# Rocky_Switch_Relay_Shield.net
KiCad netlist of a schematic drawn in EAGLE
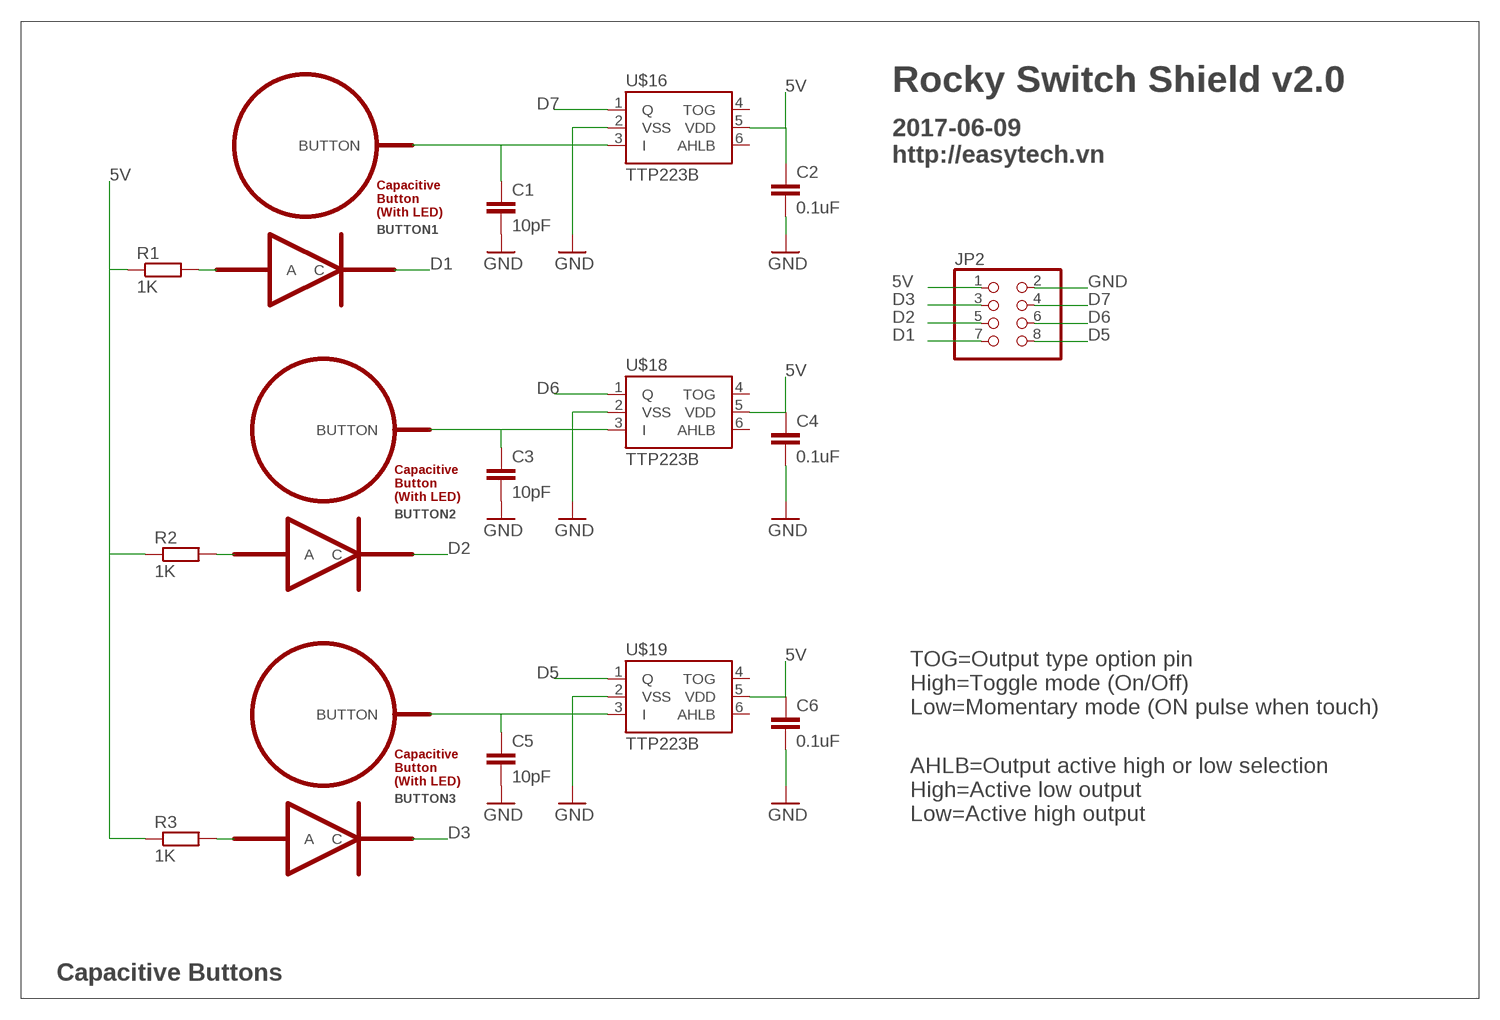
[diagram p0: schematic, sheet 1]

(export (version "E")
  (design (tool "Eeschema 10.0.6"))
  (components
    (comp (ref "BUTTON1")
      (value "BUTTON_PASSIVE_LED")
      (footprint "eagle-import:BUTTON_PASSIVE_LED")
      (libsource (lib "eagle-import") (part "BUTTON_PASSIVE_LED"))
    )
    (comp (ref "BUTTON2")
      (value "BUTTON_PASSIVE_LED")
      (footprint "eagle-import:BUTTON_PASSIVE_LED")
      (libsource (lib "eagle-import") (part "BUTTON_PASSIVE_LED"))
    )
    (comp (ref "BUTTON3")
      (value "BUTTON_PASSIVE_LED")
      (footprint "eagle-import:BUTTON_PASSIVE_LED")
      (libsource (lib "eagle-import") (part "BUTTON_PASSIVE_LED"))
    )
    (comp (ref "C1")
      (value "10pF")
      (footprint "eagle-import:C0805K")
      (libsource (lib "eagle-import") (part "C-EUC0805K"))
    )
    (comp (ref "C2")
      (value "0.1uF")
      (footprint "eagle-import:C0805K")
      (libsource (lib "eagle-import") (part "C-EUC0805K"))
    )
    (comp (ref "C3")
      (value "10pF")
      (footprint "eagle-import:C0805K")
      (libsource (lib "eagle-import") (part "C-EUC0805K"))
    )
    (comp (ref "C4")
      (value "0.1uF")
      (footprint "eagle-import:C0805K")
      (libsource (lib "eagle-import") (part "C-EUC0805K"))
    )
    (comp (ref "C5")
      (value "10pF")
      (footprint "eagle-import:C0805K")
      (libsource (lib "eagle-import") (part "C-EUC0805K"))
    )
    (comp (ref "C6")
      (value "0.1uF")
      (footprint "eagle-import:C0805K")
      (libsource (lib "eagle-import") (part "C-EUC0805K"))
    )
    (comp (ref "JP2")
      (value "PINHD-2X4")
      (footprint "eagle-import:2X04")
      (libsource (lib "eagle-import") (part "PINHD-2X4"))
    )
    (comp (ref "R1")
      (value "1K")
      (footprint "eagle-import:R0805")
      (libsource (lib "eagle-import") (part "R-EU_R0805"))
    )
    (comp (ref "R2")
      (value "1K")
      (footprint "eagle-import:R0805")
      (libsource (lib "eagle-import") (part "R-EU_R0805"))
    )
    (comp (ref "R3")
      (value "1K")
      (footprint "eagle-import:R0805")
      (libsource (lib "eagle-import") (part "R-EU_R0805"))
    )
    (comp (ref "U$16")
      (value "TTP223B")
      (footprint "eagle-import:SOT23-6")
      (libsource (lib "eagle-import") (part "TTP223B"))
    )
    (comp (ref "U$18")
      (value "TTP223B")
      (footprint "eagle-import:SOT23-6")
      (libsource (lib "eagle-import") (part "TTP223B"))
    )
    (comp (ref "U$19")
      (value "TTP223B")
      (footprint "eagle-import:SOT23-6")
      (libsource (lib "eagle-import") (part "TTP223B"))
    )
  )
  (nets
    (net (code "1") (name "/5V") (class "Default")
      (node (ref "C2") (pin "1") (pinfunction "1_1") (pintype "passive"))
      (node (ref "C4") (pin "1") (pinfunction "1_1") (pintype "passive"))
      (node (ref "C6") (pin "1") (pinfunction "1_1") (pintype "passive"))
      (node (ref "JP2") (pin "1") (pinfunction "1_1") (pintype "passive"))
      (node (ref "R1") (pin "1") (pinfunction "1_1") (pintype "passive"))
      (node (ref "R2") (pin "1") (pinfunction "1_1") (pintype "passive"))
      (node (ref "R3") (pin "1") (pinfunction "1_1") (pintype "passive"))
      (node (ref "U$16") (pin "5") (pinfunction "VDD_5") (pintype "bidirectional"))
      (node (ref "U$18") (pin "5") (pinfunction "VDD_5") (pintype "bidirectional"))
      (node (ref "U$19") (pin "5") (pinfunction "VDD_5") (pintype "bidirectional"))
    )
    (net (code "2") (name "/D1") (class "Default")
      (node (ref "BUTTON1") (pin "C") (pinfunction "C_C") (pintype "bidirectional"))
      (node (ref "JP2") (pin "7") (pinfunction "7_7") (pintype "passive"))
    )
    (net (code "3") (name "/D2") (class "Default")
      (node (ref "BUTTON2") (pin "C") (pinfunction "C_C") (pintype "bidirectional"))
      (node (ref "JP2") (pin "5") (pinfunction "5_5") (pintype "passive"))
    )
    (net (code "4") (name "/D3") (class "Default")
      (node (ref "BUTTON3") (pin "C") (pinfunction "C_C") (pintype "bidirectional"))
      (node (ref "JP2") (pin "3") (pinfunction "3_3") (pintype "passive"))
    )
    (net (code "5") (name "/D5") (class "Default")
      (node (ref "JP2") (pin "8") (pinfunction "8_8") (pintype "passive"))
      (node (ref "U$19") (pin "1") (pinfunction "Q_1") (pintype "bidirectional"))
    )
    (net (code "6") (name "/D6") (class "Default")
      (node (ref "JP2") (pin "6") (pinfunction "6_6") (pintype "passive"))
      (node (ref "U$18") (pin "1") (pinfunction "Q_1") (pintype "bidirectional"))
    )
    (net (code "7") (name "/D7") (class "Default")
      (node (ref "JP2") (pin "4") (pinfunction "4_4") (pintype "passive"))
      (node (ref "U$16") (pin "1") (pinfunction "Q_1") (pintype "bidirectional"))
    )
    (net (code "8") (name "GND") (class "Default")
      (node (ref "C1") (pin "2") (pinfunction "2_2") (pintype "passive"))
      (node (ref "C2") (pin "2") (pinfunction "2_2") (pintype "passive"))
      (node (ref "C3") (pin "2") (pinfunction "2_2") (pintype "passive"))
      (node (ref "C4") (pin "2") (pinfunction "2_2") (pintype "passive"))
      (node (ref "C5") (pin "2") (pinfunction "2_2") (pintype "passive"))
      (node (ref "C6") (pin "2") (pinfunction "2_2") (pintype "passive"))
      (node (ref "JP2") (pin "2") (pinfunction "2_2") (pintype "passive"))
      (node (ref "U$16") (pin "2") (pinfunction "VSS_2") (pintype "bidirectional"))
      (node (ref "U$18") (pin "2") (pinfunction "VSS_2") (pintype "bidirectional"))
      (node (ref "U$19") (pin "2") (pinfunction "VSS_2") (pintype "bidirectional"))
    )
    (net (code "9") (name "Net-(BUTTON1-PadA)") (class "Default")
      (node (ref "BUTTON1") (pin "A") (pinfunction "A_A") (pintype "bidirectional"))
      (node (ref "R1") (pin "2") (pinfunction "2_2") (pintype "passive"))
    )
    (net (code "10") (name "Net-(BUTTON2-PadA)") (class "Default")
      (node (ref "BUTTON2") (pin "A") (pinfunction "A_A") (pintype "bidirectional"))
      (node (ref "R2") (pin "2") (pinfunction "2_2") (pintype "passive"))
    )
    (net (code "11") (name "Net-(BUTTON3-PadA)") (class "Default")
      (node (ref "BUTTON3") (pin "A") (pinfunction "A_A") (pintype "bidirectional"))
      (node (ref "R3") (pin "2") (pinfunction "2_2") (pintype "passive"))
    )
    (net (code "12") (name "Net-(U$16-I)") (class "Default")
      (node (ref "BUTTON1") (pin "BUTTON") (pinfunction "BUTTON_BUTTON") (pintype "passive"))
      (node (ref "C1") (pin "1") (pinfunction "1_1") (pintype "passive"))
      (node (ref "U$16") (pin "3") (pinfunction "I_3") (pintype "bidirectional"))
    )
    (net (code "13") (name "Net-(U$18-I)") (class "Default")
      (node (ref "BUTTON2") (pin "BUTTON") (pinfunction "BUTTON_BUTTON") (pintype "passive"))
      (node (ref "C3") (pin "1") (pinfunction "1_1") (pintype "passive"))
      (node (ref "U$18") (pin "3") (pinfunction "I_3") (pintype "bidirectional"))
    )
    (net (code "14") (name "Net-(U$19-I)") (class "Default")
      (node (ref "BUTTON3") (pin "BUTTON") (pinfunction "BUTTON_BUTTON") (pintype "passive"))
      (node (ref "C5") (pin "1") (pinfunction "1_1") (pintype "passive"))
      (node (ref "U$19") (pin "3") (pinfunction "I_3") (pintype "bidirectional"))
    )
    (net (code "15") (name "unconnected-(U$16-AHLB-Pad6)") (class "Default")
      (node (ref "U$16") (pin "6") (pinfunction "AHLB_6") (pintype "bidirectional"))
    )
    (net (code "16") (name "unconnected-(U$16-TOG-Pad4)") (class "Default")
      (node (ref "U$16") (pin "4") (pinfunction "TOG_4") (pintype "bidirectional"))
    )
    (net (code "17") (name "unconnected-(U$18-AHLB-Pad6)") (class "Default")
      (node (ref "U$18") (pin "6") (pinfunction "AHLB_6") (pintype "bidirectional"))
    )
    (net (code "18") (name "unconnected-(U$18-TOG-Pad4)") (class "Default")
      (node (ref "U$18") (pin "4") (pinfunction "TOG_4") (pintype "bidirectional"))
    )
    (net (code "19") (name "unconnected-(U$19-AHLB-Pad6)") (class "Default")
      (node (ref "U$19") (pin "6") (pinfunction "AHLB_6") (pintype "bidirectional"))
    )
    (net (code "20") (name "unconnected-(U$19-TOG-Pad4)") (class "Default")
      (node (ref "U$19") (pin "4") (pinfunction "TOG_4") (pintype "bidirectional"))
    )
  )
)
